# Micromouse_controller_v001.net
KiCad netlist of a schematic drawn in EAGLE
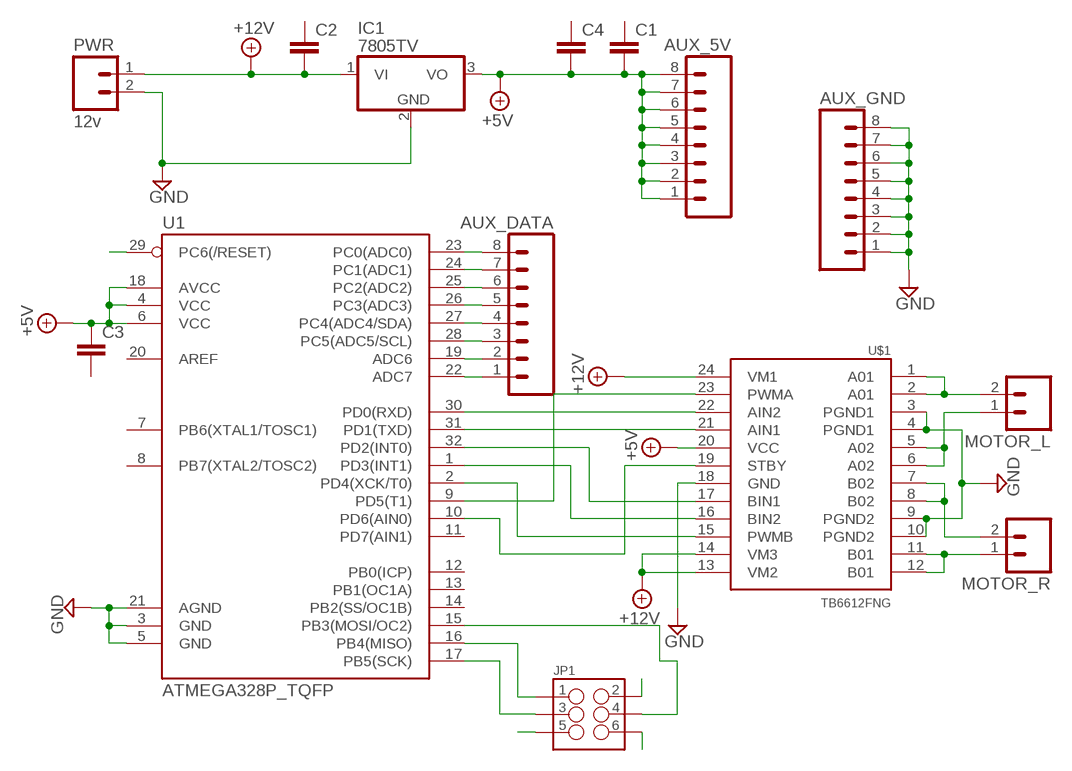
[diagram p0: schematic, sheet 1]

(export (version "E")
  (design (tool "Eeschema 10.0.6"))
  (components
    (comp (ref "AUX_5V")
      (value "M08SMD-STRAIGHT-ALT-FEMALE")
      (footprint "eagle-import:1X08_SMD_ALT")
      (libsource (lib "eagle-import") (part "M08SMD-STRAIGHT-ALT-FEMALE"))
    )
    (comp (ref "AUX_DATA")
      (value "M08SMD-STRAIGHT-ALT-FEMALE")
      (footprint "eagle-import:1X08_SMD_ALT")
      (libsource (lib "eagle-import") (part "M08SMD-STRAIGHT-ALT-FEMALE"))
    )
    (comp (ref "AUX_GND")
      (value "M08SMD-STRAIGHT-ALT-FEMALE")
      (footprint "eagle-import:1X08_SMD_ALT")
      (libsource (lib "eagle-import") (part "M08SMD-STRAIGHT-ALT-FEMALE"))
    )
    (comp (ref "C1")
      (value "CAPSMD")
      (footprint "eagle-import:GRM43D")
      (libsource (lib "eagle-import") (part "CAPSMD"))
    )
    (comp (ref "C2")
      (value "CAPSMD")
      (footprint "eagle-import:GRM43D")
      (libsource (lib "eagle-import") (part "CAPSMD"))
    )
    (comp (ref "C3")
      (value "CAPSMD")
      (footprint "eagle-import:GRM43D")
      (libsource (lib "eagle-import") (part "CAPSMD"))
    )
    (comp (ref "C4")
      (value "CAPSMD")
      (footprint "eagle-import:GRM43D")
      (libsource (lib "eagle-import") (part "CAPSMD"))
    )
    (comp (ref "IC1")
      (value "7805TV")
      (footprint "eagle-import:TO220V")
      (libsource (lib "eagle-import") (part "78TV05"))
    )
    (comp (ref "JP1")
      (value "M03X2FEMALE_SMD")
      (footprint "eagle-import:2X3_SMD")
      (libsource (lib "eagle-import") (part "M03X2FEMALE_SMD"))
    )
    (comp (ref "MOTOR_L")
      (value "M02-JST-2MM-SMT")
      (footprint "eagle-import:JST-2-SMD")
      (libsource (lib "eagle-import") (part "M02-JST-2MM-SMT"))
    )
    (comp (ref "MOTOR_R")
      (value "M02-JST-2MM-SMT")
      (footprint "eagle-import:JST-2-SMD")
      (libsource (lib "eagle-import") (part "M02-JST-2MM-SMT"))
    )
    (comp (ref "PWR")
      (value "12v")
      (footprint "eagle-import:JST-2-SMD")
      (libsource (lib "eagle-import") (part "M02-JST-2MM-SMT"))
    )
    (comp (ref "U$1")
      (value "TB6612FNG")
      (footprint "eagle-import:SSOP24")
      (libsource (lib "eagle-import") (part "TB6612FNG"))
    )
    (comp (ref "U1")
      (value "ATMEGA328P_TQFP")
      (footprint "eagle-import:TQFP32-08")
      (libsource (lib "eagle-import") (part "ATMEGA328P_TQFP"))
    )
  )
  (nets
    (net (code "1") (name "+5V") (class "Default")
      (node (ref "AUX_5V") (pin "1") (pinfunction "1_1") (pintype "passive"))
      (node (ref "AUX_5V") (pin "2") (pinfunction "2_2") (pintype "passive"))
      (node (ref "AUX_5V") (pin "3") (pinfunction "3_3") (pintype "passive"))
      (node (ref "AUX_5V") (pin "4") (pinfunction "4_4") (pintype "passive"))
      (node (ref "AUX_5V") (pin "5") (pinfunction "5_5") (pintype "passive"))
      (node (ref "AUX_5V") (pin "6") (pinfunction "6_6") (pintype "passive"))
      (node (ref "AUX_5V") (pin "7") (pinfunction "7_7") (pintype "passive"))
      (node (ref "AUX_5V") (pin "8") (pinfunction "8_8") (pintype "passive"))
      (node (ref "C1") (pin "C") (pinfunction "2_C") (pintype "passive"))
      (node (ref "C3") (pin "A") (pinfunction "1_A") (pintype "passive"))
      (node (ref "C4") (pin "C") (pinfunction "2_C") (pintype "passive"))
      (node (ref "IC1") (pin "3") (pinfunction "VO_3") (pintype "passive"))
      (node (ref "JP1") (pin "2") (pinfunction "2_2") (pintype "bidirectional"))
      (node (ref "U$1") (pin "20") (pinfunction "VCC_20") (pintype "bidirectional"))
      (node (ref "U1") (pin "18") (pinfunction "AVCC_18") (pintype "bidirectional"))
      (node (ref "U1") (pin "4") (pinfunction "VCC_4") (pintype "bidirectional"))
      (node (ref "U1") (pin "6") (pinfunction "VCC_6") (pintype "bidirectional"))
    )
    (net (code "2") (name "+12V") (class "Default")
      (node (ref "C2") (pin "C") (pinfunction "2_C") (pintype "passive"))
      (node (ref "IC1") (pin "1") (pinfunction "VI_1") (pintype "input"))
      (node (ref "PWR") (pin "1") (pinfunction "2_1") (pintype "passive"))
      (node (ref "U$1") (pin "13") (pinfunction "VM2_13") (pintype "bidirectional"))
      (node (ref "U$1") (pin "14") (pinfunction "VM3_14") (pintype "bidirectional"))
      (node (ref "U$1") (pin "24") (pinfunction "VM1_24") (pintype "bidirectional"))
    )
    (net (code "3") (name "/RST") (class "Default")
      (node (ref "JP1") (pin "5") (pinfunction "5_5") (pintype "bidirectional"))
      (node (ref "U1") (pin "29") (pinfunction "PC6(/RESET)_29") (pintype "bidirectional"))
    )
    (net (code "4") (name "GND") (class "Default")
      (node (ref "AUX_GND") (pin "1") (pinfunction "1_1") (pintype "passive"))
      (node (ref "AUX_GND") (pin "2") (pinfunction "2_2") (pintype "passive"))
      (node (ref "AUX_GND") (pin "3") (pinfunction "3_3") (pintype "passive"))
      (node (ref "AUX_GND") (pin "4") (pinfunction "4_4") (pintype "passive"))
      (node (ref "AUX_GND") (pin "5") (pinfunction "5_5") (pintype "passive"))
      (node (ref "AUX_GND") (pin "6") (pinfunction "6_6") (pintype "passive"))
      (node (ref "AUX_GND") (pin "7") (pinfunction "7_7") (pintype "passive"))
      (node (ref "AUX_GND") (pin "8") (pinfunction "8_8") (pintype "passive"))
      (node (ref "IC1") (pin "2") (pinfunction "GND_2") (pintype "passive"))
      (node (ref "JP1") (pin "6") (pinfunction "6_6") (pintype "bidirectional"))
      (node (ref "PWR") (pin "2") (pinfunction "1_2") (pintype "passive"))
      (node (ref "U$1") (pin "10") (pinfunction "PGND2_10") (pintype "bidirectional"))
      (node (ref "U$1") (pin "18") (pinfunction "GND_18") (pintype "bidirectional"))
      (node (ref "U$1") (pin "3") (pinfunction "PGND1_3") (pintype "bidirectional"))
      (node (ref "U$1") (pin "4") (pinfunction "PGND1_4") (pintype "bidirectional"))
      (node (ref "U$1") (pin "9") (pinfunction "PGND2_9") (pintype "bidirectional"))
      (node (ref "U1") (pin "21") (pinfunction "AGND_21") (pintype "bidirectional"))
      (node (ref "U1") (pin "3") (pinfunction "GND_3") (pintype "bidirectional"))
      (node (ref "U1") (pin "5") (pinfunction "GND_5") (pintype "bidirectional"))
    )
    (net (code "5") (name "Net-(MOTOR_L-1)") (class "Default")
      (node (ref "MOTOR_L") (pin "2") (pinfunction "1_2") (pintype "passive"))
      (node (ref "U$1") (pin "1") (pinfunction "A01_1") (pintype "bidirectional"))
      (node (ref "U$1") (pin "2") (pinfunction "A01_2") (pintype "bidirectional"))
    )
    (net (code "6") (name "Net-(MOTOR_L-2)") (class "Default")
      (node (ref "MOTOR_L") (pin "1") (pinfunction "2_1") (pintype "passive"))
      (node (ref "U$1") (pin "5") (pinfunction "A02_5") (pintype "bidirectional"))
      (node (ref "U$1") (pin "6") (pinfunction "A02_6") (pintype "bidirectional"))
    )
    (net (code "7") (name "Net-(MOTOR_R-1)") (class "Default")
      (node (ref "MOTOR_R") (pin "2") (pinfunction "1_2") (pintype "passive"))
      (node (ref "U$1") (pin "7") (pinfunction "B02_7") (pintype "bidirectional"))
      (node (ref "U$1") (pin "8") (pinfunction "B02_8") (pintype "bidirectional"))
    )
    (net (code "8") (name "Net-(MOTOR_R-2)") (class "Default")
      (node (ref "MOTOR_R") (pin "1") (pinfunction "2_1") (pintype "passive"))
      (node (ref "U$1") (pin "11") (pinfunction "B01_11") (pintype "bidirectional"))
      (node (ref "U$1") (pin "12") (pinfunction "B01_12") (pintype "bidirectional"))
    )
    (net (code "9") (name "Net-(U$1-AIN1)") (class "Default")
      (node (ref "U$1") (pin "21") (pinfunction "AIN1_21") (pintype "bidirectional"))
      (node (ref "U1") (pin "31") (pinfunction "PD1(TXD)_31") (pintype "bidirectional"))
    )
    (net (code "10") (name "Net-(U$1-AIN2)") (class "Default")
      (node (ref "U$1") (pin "22") (pinfunction "AIN2_22") (pintype "bidirectional"))
      (node (ref "U1") (pin "30") (pinfunction "PD0(RXD)_30") (pintype "bidirectional"))
    )
    (net (code "11") (name "Net-(U$1-BIN1)") (class "Default")
      (node (ref "U$1") (pin "17") (pinfunction "BIN1_17") (pintype "bidirectional"))
      (node (ref "U1") (pin "32") (pinfunction "PD2(INT0)_32") (pintype "bidirectional"))
    )
    (net (code "12") (name "Net-(U$1-BIN2)") (class "Default")
      (node (ref "U$1") (pin "16") (pinfunction "BIN2_16") (pintype "bidirectional"))
      (node (ref "U1") (pin "1") (pinfunction "PD3(INT1)_1") (pintype "bidirectional"))
    )
    (net (code "13") (name "Net-(U$1-PWMA)") (class "Default")
      (node (ref "U$1") (pin "23") (pinfunction "PWMA_23") (pintype "bidirectional"))
      (node (ref "U1") (pin "9") (pinfunction "PD5(T1)_9") (pintype "bidirectional"))
    )
    (net (code "14") (name "Net-(U$1-PWMB)") (class "Default")
      (node (ref "U$1") (pin "15") (pinfunction "PWMB_15") (pintype "bidirectional"))
      (node (ref "U1") (pin "2") (pinfunction "PD4(XCK/T0)_2") (pintype "bidirectional"))
    )
    (net (code "15") (name "Net-(U$1-STBY)") (class "Default")
      (node (ref "U$1") (pin "19") (pinfunction "STBY_19") (pintype "bidirectional"))
      (node (ref "U1") (pin "10") (pinfunction "PD6(AIN0)_10") (pintype "bidirectional"))
    )
    (net (code "16") (name "Net-(U1-ADC6)") (class "Default")
      (node (ref "AUX_DATA") (pin "2") (pinfunction "2_2") (pintype "passive"))
      (node (ref "U1") (pin "19") (pinfunction "ADC6_19") (pintype "bidirectional"))
    )
    (net (code "17") (name "Net-(U1-ADC7)") (class "Default")
      (node (ref "AUX_DATA") (pin "1") (pinfunction "1_1") (pintype "passive"))
      (node (ref "U1") (pin "22") (pinfunction "ADC7_22") (pintype "bidirectional"))
    )
    (net (code "18") (name "Net-(U1-PB3(MOSI{slash}OC2))") (class "Default")
      (node (ref "JP1") (pin "4") (pinfunction "4_4") (pintype "bidirectional"))
      (node (ref "U1") (pin "15") (pinfunction "PB3(MOSI/OC2)_15") (pintype "bidirectional"))
    )
    (net (code "19") (name "Net-(U1-PB4(MISO))") (class "Default")
      (node (ref "JP1") (pin "1") (pinfunction "1_1") (pintype "bidirectional"))
      (node (ref "U1") (pin "16") (pinfunction "PB4(MISO)_16") (pintype "bidirectional"))
    )
    (net (code "20") (name "Net-(U1-PB5(SCK))") (class "Default")
      (node (ref "JP1") (pin "3") (pinfunction "3_3") (pintype "bidirectional"))
      (node (ref "U1") (pin "17") (pinfunction "PB5(SCK)_17") (pintype "bidirectional"))
    )
    (net (code "21") (name "Net-(U1-PC0(ADC0))") (class "Default")
      (node (ref "AUX_DATA") (pin "8") (pinfunction "8_8") (pintype "passive"))
      (node (ref "U1") (pin "23") (pinfunction "PC0(ADC0)_23") (pintype "bidirectional"))
    )
    (net (code "22") (name "Net-(U1-PC1(ADC1))") (class "Default")
      (node (ref "AUX_DATA") (pin "7") (pinfunction "7_7") (pintype "passive"))
      (node (ref "U1") (pin "24") (pinfunction "PC1(ADC1)_24") (pintype "bidirectional"))
    )
    (net (code "23") (name "Net-(U1-PC2(ADC2))") (class "Default")
      (node (ref "AUX_DATA") (pin "6") (pinfunction "6_6") (pintype "passive"))
      (node (ref "U1") (pin "25") (pinfunction "PC2(ADC2)_25") (pintype "bidirectional"))
    )
    (net (code "24") (name "Net-(U1-PC3(ADC3))") (class "Default")
      (node (ref "AUX_DATA") (pin "5") (pinfunction "5_5") (pintype "passive"))
      (node (ref "U1") (pin "26") (pinfunction "PC3(ADC3)_26") (pintype "bidirectional"))
    )
    (net (code "25") (name "Net-(U1-PC4(ADC4{slash}SDA))") (class "Default")
      (node (ref "AUX_DATA") (pin "4") (pinfunction "4_4") (pintype "passive"))
      (node (ref "U1") (pin "27") (pinfunction "PC4(ADC4/SDA)_27") (pintype "bidirectional"))
    )
    (net (code "26") (name "Net-(U1-PC5(ADC5{slash}SCL))") (class "Default")
      (node (ref "AUX_DATA") (pin "3") (pinfunction "3_3") (pintype "passive"))
      (node (ref "U1") (pin "28") (pinfunction "PC5(ADC5/SCL)_28") (pintype "bidirectional"))
    )
    (net (code "27") (name "unconnected-(C1-1-PadA)") (class "Default")
      (node (ref "C1") (pin "A") (pinfunction "1_A") (pintype "passive"))
    )
    (net (code "28") (name "unconnected-(C2-1-PadA)") (class "Default")
      (node (ref "C2") (pin "A") (pinfunction "1_A") (pintype "passive"))
    )
    (net (code "29") (name "unconnected-(C3-2-PadC)") (class "Default")
      (node (ref "C3") (pin "C") (pinfunction "2_C") (pintype "passive"))
    )
    (net (code "30") (name "unconnected-(C4-1-PadA)") (class "Default")
      (node (ref "C4") (pin "A") (pinfunction "1_A") (pintype "passive"))
    )
    (net (code "31") (name "unconnected-(U1-AREF-Pad20)") (class "Default")
      (node (ref "U1") (pin "20") (pinfunction "AREF_20") (pintype "bidirectional"))
    )
    (net (code "32") (name "unconnected-(U1-PB0(ICP)-Pad12)") (class "Default")
      (node (ref "U1") (pin "12") (pinfunction "PB0(ICP)_12") (pintype "bidirectional"))
    )
    (net (code "33") (name "unconnected-(U1-PB1(OC1A)-Pad13)") (class "Default")
      (node (ref "U1") (pin "13") (pinfunction "PB1(OC1A)_13") (pintype "bidirectional"))
    )
    (net (code "34") (name "unconnected-(U1-PB2(SS{slash}OC1B)-Pad14)") (class "Default")
      (node (ref "U1") (pin "14") (pinfunction "PB2(SS/OC1B)_14") (pintype "bidirectional"))
    )
    (net (code "35") (name "unconnected-(U1-PB6(XTAL1{slash}TOSC1)-Pad7)") (class "Default")
      (node (ref "U1") (pin "7") (pinfunction "PB6(XTAL1/TOSC1)_7") (pintype "bidirectional"))
    )
    (net (code "36") (name "unconnected-(U1-PB7(XTAL2{slash}TOSC2)-Pad8)") (class "Default")
      (node (ref "U1") (pin "8") (pinfunction "PB7(XTAL2/TOSC2)_8") (pintype "bidirectional"))
    )
    (net (code "37") (name "unconnected-(U1-PD7(AIN1)-Pad11)") (class "Default")
      (node (ref "U1") (pin "11") (pinfunction "PD7(AIN1)_11") (pintype "bidirectional"))
    )
  )
)
